# MCU.net
KiCad netlist of a schematic drawn in Altium Designer
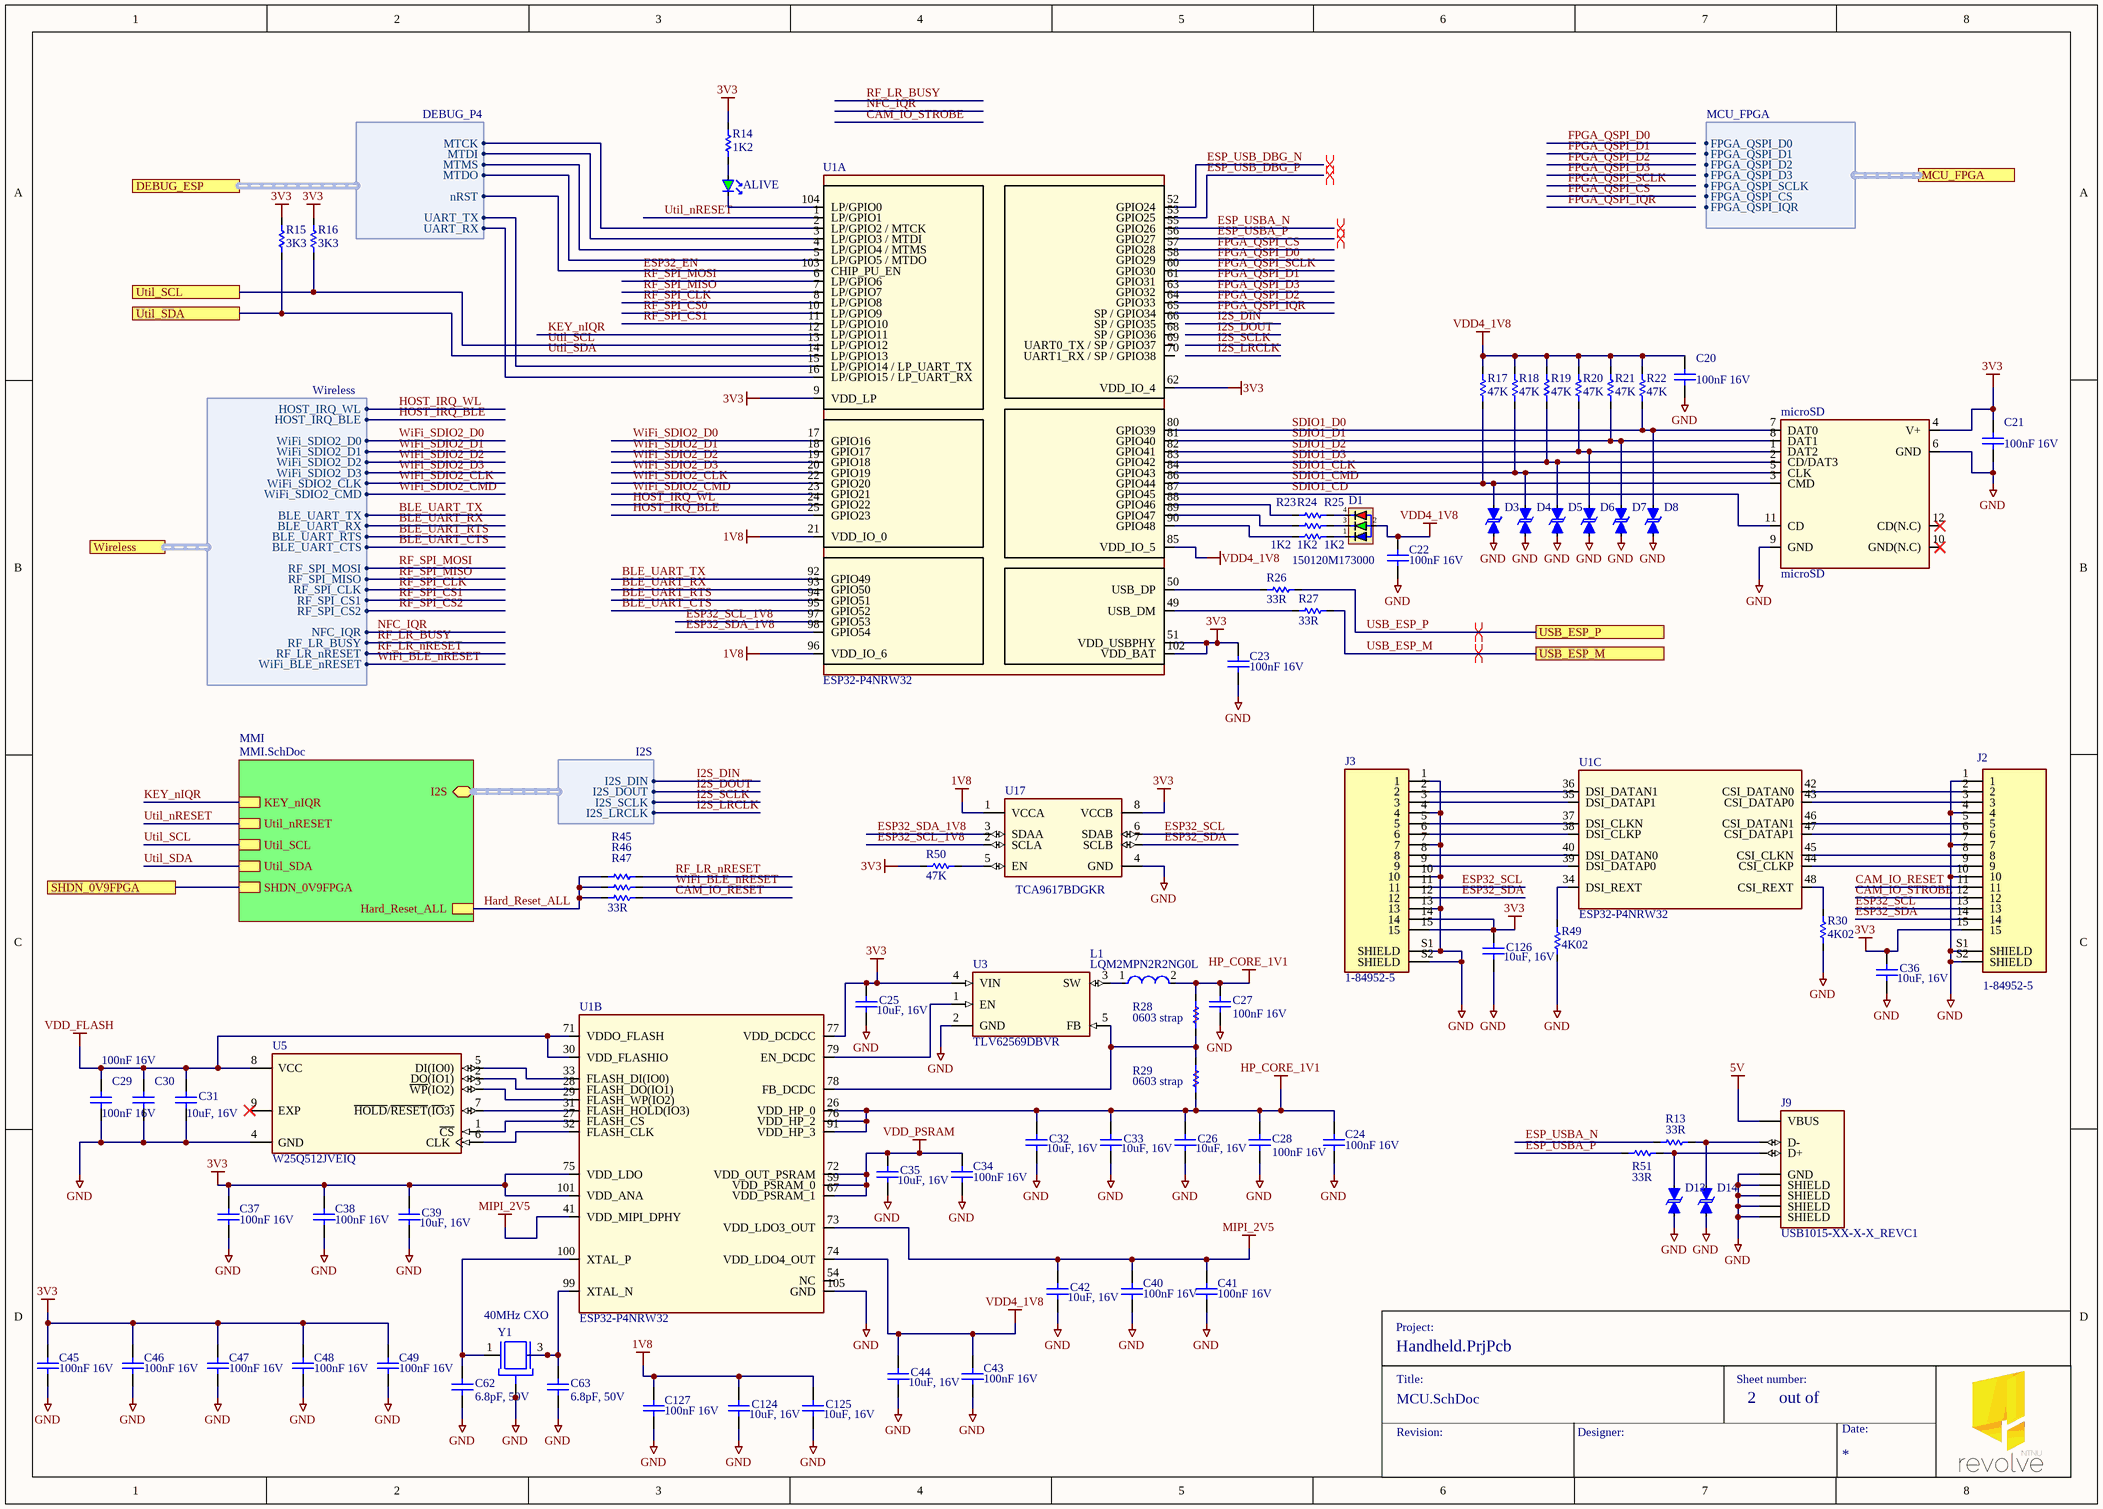
[diagram p0: MCU.SchDoc]

(export (version "E")
  (design (tool "Eeschema 10.0.6"))
  (components
    (comp (ref "ALIVE")
      (value "SMD LED 0603, Green")
      (footprint "LED-0603-RED")
      (description "0603LED-Green")
      (libsource (lib "Eirik Silnes") (part "CMP-001-C10-9"))
    )
    (comp (ref "C20") (value "100nF 16V") (footprint "0402") (libsource (lib "Revolve NTNU") (part "CAP")))
    (comp (ref "C21") (value "100nF 16V") (footprint "0402") (libsource (lib "Revolve NTNU") (part "CAP")))
    (comp (ref "C22") (value "100nF 16V") (footprint "0402") (libsource (lib "Revolve NTNU") (part "CAP")))
    (comp (ref "C23") (value "100nF 16V") (footprint "0402") (libsource (lib "Revolve NTNU") (part "CAP")))
    (comp (ref "C24") (value "100nF 16V") (footprint "0402") (libsource (lib "Revolve NTNU") (part "CAP")))
    (comp (ref "C25")
      (value "10uF, 16V")
      (footprint "0603 Capacitor")
      (description "10uF, 16V, 20%, X5R, 0603")
      (libsource (lib "Revolve NTNU") (part "CAP"))
    )
    (comp (ref "C26")
      (value "10uF, 16V")
      (footprint "0603 Capacitor")
      (description "10uF, 16V, 20%, X5R, 0603")
      (libsource (lib "Revolve NTNU") (part "CAP"))
    )
    (comp (ref "C27") (value "100nF 16V") (footprint "0402") (libsource (lib "Revolve NTNU") (part "CAP")))
    (comp (ref "C28") (value "100nF 16V") (footprint "0402") (libsource (lib "Revolve NTNU") (part "CAP")))
    (comp (ref "C29") (value "100nF 16V") (footprint "0402") (libsource (lib "Revolve NTNU") (part "CAP")))
    (comp (ref "C30") (value "100nF 16V") (footprint "0402") (libsource (lib "Revolve NTNU") (part "CAP")))
    (comp (ref "C31")
      (value "10uF, 16V")
      (footprint "0603 Capacitor")
      (description "10uF, 16V, 20%, X5R, 0603")
      (libsource (lib "Revolve NTNU") (part "CAP"))
    )
    (comp (ref "C32")
      (value "10uF, 16V")
      (footprint "0603 Capacitor")
      (description "10uF, 16V, 20%, X5R, 0603")
      (libsource (lib "Revolve NTNU") (part "CAP"))
    )
    (comp (ref "C33")
      (value "10uF, 16V")
      (footprint "0603 Capacitor")
      (description "10uF, 16V, 20%, X5R, 0603")
      (libsource (lib "Revolve NTNU") (part "CAP"))
    )
    (comp (ref "C34") (value "100nF 16V") (footprint "0402") (libsource (lib "Revolve NTNU") (part "CAP")))
    (comp (ref "C35")
      (value "10uF, 16V")
      (footprint "0603 Capacitor")
      (description "10uF, 16V, 20%, X5R, 0603")
      (libsource (lib "Revolve NTNU") (part "CAP"))
    )
    (comp (ref "C36")
      (value "10uF, 16V")
      (footprint "0603 Capacitor")
      (description "10uF, 16V, 20%, X5R, 0603")
      (libsource (lib "Revolve NTNU") (part "CAP"))
    )
    (comp (ref "C37") (value "100nF 16V") (footprint "0402") (libsource (lib "Revolve NTNU") (part "CAP")))
    (comp (ref "C38") (value "100nF 16V") (footprint "0402") (libsource (lib "Revolve NTNU") (part "CAP")))
    (comp (ref "C39")
      (value "10uF, 16V")
      (footprint "0603 Capacitor")
      (description "10uF, 16V, 20%, X5R, 0603")
      (libsource (lib "Revolve NTNU") (part "CAP"))
    )
    (comp (ref "C40") (value "100nF 16V") (footprint "0402") (libsource (lib "Revolve NTNU") (part "CAP")))
    (comp (ref "C41") (value "100nF 16V") (footprint "0402") (libsource (lib "Revolve NTNU") (part "CAP")))
    (comp (ref "C42")
      (value "10uF, 16V")
      (footprint "0603 Capacitor")
      (description "10uF, 16V, 20%, X5R, 0603")
      (libsource (lib "Revolve NTNU") (part "CAP"))
    )
    (comp (ref "C43") (value "100nF 16V") (footprint "0402") (libsource (lib "Revolve NTNU") (part "CAP")))
    (comp (ref "C44")
      (value "10uF, 16V")
      (footprint "0603 Capacitor")
      (description "10uF, 16V, 20%, X5R, 0603")
      (libsource (lib "Revolve NTNU") (part "CAP"))
    )
    (comp (ref "C45") (value "100nF 16V") (footprint "0402") (libsource (lib "Revolve NTNU") (part "CAP")))
    (comp (ref "C46") (value "100nF 16V") (footprint "0402") (libsource (lib "Revolve NTNU") (part "CAP")))
    (comp (ref "C47") (value "100nF 16V") (footprint "0402") (libsource (lib "Revolve NTNU") (part "CAP")))
    (comp (ref "C48") (value "100nF 16V") (footprint "0402") (libsource (lib "Revolve NTNU") (part "CAP")))
    (comp (ref "C49") (value "100nF 16V") (footprint "0402") (libsource (lib "Revolve NTNU") (part "CAP")))
    (comp (ref "C62")
      (value "6.8pF, 50V")
      (footprint "0402 resistor")
      (description "6.8pF, 50V, 10%, 0402")
      (libsource (lib "Revolve NTNU") (part "CAP"))
    )
    (comp (ref "C63")
      (value "6.8pF, 50V")
      (footprint "0402 resistor")
      (description "6.8pF, 50V, 10%, 0402")
      (libsource (lib "Revolve NTNU") (part "CAP"))
    )
    (comp (ref "C124")
      (value "10uF, 16V")
      (footprint "0603 Capacitor")
      (description "10uF, 16V, 20%, X5R, 0603")
      (libsource (lib "Revolve NTNU") (part "CAP"))
    )
    (comp (ref "C125")
      (value "10uF, 16V")
      (footprint "0603 Capacitor")
      (description "10uF, 16V, 20%, X5R, 0603")
      (libsource (lib "Revolve NTNU") (part "CAP"))
    )
    (comp (ref "C126")
      (value "10uF, 16V")
      (footprint "0603 Capacitor")
      (description "10uF, 16V, 20%, X5R, 0603")
      (libsource (lib "Revolve NTNU") (part "CAP"))
    )
    (comp (ref "C127") (value "100nF 16V") (footprint "0402") (libsource (lib "Revolve NTNU") (part "CAP")))
    (comp (ref "D1")
      (value "150120M173000")
      (footprint "WL-SFCW_1206")
      (description "Led, Red/Green/Blue, 360Mcd/1Cd/350Mcd Rohs Compliant: Yes")
      (libsource (lib "Eirik Silnes") (part "WL-SFCW_type 2"))
    )
    (comp (ref "D3")
      (value "DESD3V3E1BL-7B")
      (footprint "CR_X1-DFN1006-2_DIO-M")
      (description "TVS DIODE 3.3V, DFN1006-2, 13pF @ 1MHz")
      (fields (field (name "COPYRIGHT") "Copyright (C) 2025 Ultra Librarian. All rights reserved."))
      (libsource (lib "Handheld") (part "DESD3V3E1BL-7B"))
    )
    (comp (ref "D4")
      (value "DESD3V3E1BL-7B")
      (footprint "CR_X1-DFN1006-2_DIO-M")
      (description "TVS DIODE 3.3V, DFN1006-2, 13pF @ 1MHz")
      (fields (field (name "COPYRIGHT") "Copyright (C) 2025 Ultra Librarian. All rights reserved."))
      (libsource (lib "Handheld") (part "DESD3V3E1BL-7B"))
    )
    (comp (ref "D5")
      (value "DESD3V3E1BL-7B")
      (footprint "CR_X1-DFN1006-2_DIO-M")
      (description "TVS DIODE 3.3V, DFN1006-2, 13pF @ 1MHz")
      (fields (field (name "COPYRIGHT") "Copyright (C) 2025 Ultra Librarian. All rights reserved."))
      (libsource (lib "Handheld") (part "DESD3V3E1BL-7B"))
    )
    (comp (ref "D6")
      (value "DESD3V3E1BL-7B")
      (footprint "CR_X1-DFN1006-2_DIO-M")
      (description "TVS DIODE 3.3V, DFN1006-2, 13pF @ 1MHz")
      (fields (field (name "COPYRIGHT") "Copyright (C) 2025 Ultra Librarian. All rights reserved."))
      (libsource (lib "Handheld") (part "DESD3V3E1BL-7B"))
    )
    (comp (ref "D7")
      (value "DESD3V3E1BL-7B")
      (footprint "CR_X1-DFN1006-2_DIO-M")
      (description "TVS DIODE 3.3V, DFN1006-2, 13pF @ 1MHz")
      (fields (field (name "COPYRIGHT") "Copyright (C) 2025 Ultra Librarian. All rights reserved."))
      (libsource (lib "Handheld") (part "DESD3V3E1BL-7B"))
    )
    (comp (ref "D8")
      (value "DESD3V3E1BL-7B")
      (footprint "CR_X1-DFN1006-2_DIO-M")
      (description "TVS DIODE 3.3V, DFN1006-2, 13pF @ 1MHz")
      (fields (field (name "COPYRIGHT") "Copyright (C) 2025 Ultra Librarian. All rights reserved."))
      (libsource (lib "Handheld") (part "DESD3V3E1BL-7B"))
    )
    (comp (ref "D13")
      (value "DESD3V3E1BL-7B")
      (footprint "CR_X1-DFN1006-2_DIO-M")
      (description "TVS DIODE 3.3V, DFN1006-2, 13pF @ 1MHz")
      (fields (field (name "COPYRIGHT") "Copyright (C) 2025 Ultra Librarian. All rights reserved."))
      (libsource (lib "Handheld") (part "DESD3V3E1BL-7B"))
    )
    (comp (ref "D14")
      (value "DESD3V3E1BL-7B")
      (footprint "CR_X1-DFN1006-2_DIO-M")
      (description "TVS DIODE 3.3V, DFN1006-2, 13pF @ 1MHz")
      (fields (field (name "COPYRIGHT") "Copyright (C) 2025 Ultra Librarian. All rights reserved."))
      (libsource (lib "Handheld") (part "DESD3V3E1BL-7B"))
    )
    (comp (ref "J2")
      (value "1-84952-5")
      (footprint "TE_1-84952-5")
      (description "Conn FPC Connector SKT 15 POS 1mm Solder RA SMD T/R")
      (fields (field (name "MF") "TE Connectivity"))
      (libsource (lib "Handheld") (part "1-84952-5"))
    )
    (comp (ref "J3")
      (value "1-84952-5")
      (footprint "TE_1-84952-5")
      (description "Conn FPC Connector SKT 15 POS 1mm Solder RA SMD T/R")
      (fields (field (name "MF") "TE Connectivity"))
      (libsource (lib "") (part "1-84952-5_1"))
    )
    (comp (ref "J9")
      (value "USB1015-XX-X-X_REVC1")
      (footprint "GCT_USB1015-XX-X-X_REVC1")
      (fields (field (name "MF") "Global Connector Technology") (field (name "MP") "USB1015-GF-L-A"))
      (libsource (lib "Handheld") (part "USB1015-XX-X-X_REVC1"))
    )
    (comp (ref "L1")
      (value "LQM2MPN2R2NG0L")
      (footprint "FP-LQM2MPN_G0-IPC_B")
      (description "Inductor Power Chip Shielded Multi-Layer 2.2uH 30% 1MHz Ferrite 1.2A 0.138Ohm DCR 0806 T/R")
      (fields (field (name "TOLERANCE") "30%"))
      (libsource (lib "Eirik Silnes") (part "725321dda6339637d4d059423bc1c3c"))
    )
    (comp (ref "microSD")
      (value "microSD")
      (footprint "Handheld:microSD")
      (description "wurth µSD connector")
      (libsource (lib "Handheld") (part "microSD"))
    )
    (comp (ref "R13")
      (value "33R")
      (footprint "0603 Resistor")
      (description "33R, 1%, 1/10W, 0603")
      (fields (field (name "TOLERANCE") "1%") (field (name "MANUFACTURER") "Panasonic"))
      (libsource (lib "Revolve NTNU") (part "Resistor"))
    )
    (comp (ref "R14")
      (value "1K2")
      (footprint "0603 Resistor")
      (description "1K2, 5%, 1/10W, 0603")
      (libsource (lib "Revolve NTNU") (part "Resistor"))
    )
    (comp (ref "R15")
      (value "3K3")
      (footprint "0603 Resistor")
      (description "3K3, 5%, 1/10W, 0603")
      (libsource (lib "Revolve NTNU") (part "Resistor"))
    )
    (comp (ref "R16")
      (value "3K3")
      (footprint "0603 Resistor")
      (description "3K3, 5%, 1/10W, 0603")
      (libsource (lib "Revolve NTNU") (part "Resistor"))
    )
    (comp (ref "R17")
      (value "47K")
      (footprint "0603 Resistor")
      (description "47K, 1%, 1/10W, 0603")
      (libsource (lib "Revolve NTNU") (part "Resistor"))
    )
    (comp (ref "R18")
      (value "47K")
      (footprint "0603 Resistor")
      (description "47K, 1%, 1/10W, 0603")
      (libsource (lib "Revolve NTNU") (part "Resistor"))
    )
    (comp (ref "R19")
      (value "47K")
      (footprint "0603 Resistor")
      (description "47K, 1%, 1/10W, 0603")
      (libsource (lib "Revolve NTNU") (part "Resistor"))
    )
    (comp (ref "R20")
      (value "47K")
      (footprint "0603 Resistor")
      (description "47K, 1%, 1/10W, 0603")
      (libsource (lib "Revolve NTNU") (part "Resistor"))
    )
    (comp (ref "R21")
      (value "47K")
      (footprint "0603 Resistor")
      (description "47K, 1%, 1/10W, 0603")
      (libsource (lib "Revolve NTNU") (part "Resistor"))
    )
    (comp (ref "R22")
      (value "47K")
      (footprint "0603 Resistor")
      (description "47K, 1%, 1/10W, 0603")
      (libsource (lib "Revolve NTNU") (part "Resistor"))
    )
    (comp (ref "R23")
      (value "1K2")
      (footprint "0603 Resistor")
      (description "1K2, 5%, 1/10W, 0603")
      (libsource (lib "Revolve NTNU") (part "Resistor"))
    )
    (comp (ref "R24")
      (value "1K2")
      (footprint "0603 Resistor")
      (description "1K2, 5%, 1/10W, 0603")
      (libsource (lib "Revolve NTNU") (part "Resistor"))
    )
    (comp (ref "R25")
      (value "1K2")
      (footprint "0603 Resistor")
      (description "1K2, 5%, 1/10W, 0603")
      (libsource (lib "Revolve NTNU") (part "Resistor"))
    )
    (comp (ref "R26")
      (value "33R")
      (footprint "0603 Resistor")
      (description "33R, 1%, 1/10W, 0603")
      (fields (field (name "TOLERANCE") "1%") (field (name "MANUFACTURER") "Panasonic"))
      (libsource (lib "Revolve NTNU") (part "Resistor"))
    )
    (comp (ref "R27")
      (value "33R")
      (footprint "0603 Resistor")
      (description "33R, 1%, 1/10W, 0603")
      (fields (field (name "TOLERANCE") "1%") (field (name "MANUFACTURER") "Panasonic"))
      (libsource (lib "Revolve NTNU") (part "Resistor"))
    )
    (comp (ref "R28")
      (value "0603 strap")
      (footprint "0603 pads")
      (description "No resistor, just the pad")
      (libsource (lib "Revolve NTNU") (part "Component_1"))
    )
    (comp (ref "R29")
      (value "0603 strap")
      (footprint "0603 pads")
      (description "No resistor, just the pad")
      (libsource (lib "Revolve NTNU") (part "Component_1"))
    )
    (comp (ref "R30")
      (value "4K02")
      (footprint "0603 Resistor")
      (description "4K02, 1%, 1/10W, 0603")
      (libsource (lib "Revolve NTNU") (part "Resistor"))
    )
    (comp (ref "R45")
      (value "33R")
      (footprint "0603 Resistor")
      (description "33R, 1%, 1/10W, 0603")
      (fields (field (name "TOLERANCE") "1%") (field (name "MANUFACTURER") "Panasonic"))
      (libsource (lib "Revolve NTNU") (part "Resistor"))
    )
    (comp (ref "R46")
      (value "33R")
      (footprint "0603 Resistor")
      (description "33R, 1%, 1/10W, 0603")
      (fields (field (name "TOLERANCE") "1%") (field (name "MANUFACTURER") "Panasonic"))
      (libsource (lib "Revolve NTNU") (part "Resistor"))
    )
    (comp (ref "R47")
      (value "33R")
      (footprint "0603 Resistor")
      (description "33R, 1%, 1/10W, 0603")
      (fields (field (name "TOLERANCE") "1%") (field (name "MANUFACTURER") "Panasonic"))
      (libsource (lib "Revolve NTNU") (part "Resistor"))
    )
    (comp (ref "R49")
      (value "4K02")
      (footprint "0603 Resistor")
      (description "4K02, 1%, 1/10W, 0603")
      (libsource (lib "Revolve NTNU") (part "Resistor"))
    )
    (comp (ref "R50")
      (value "47K")
      (footprint "0603 Resistor")
      (description "47K, 1%, 1/10W, 0603")
      (libsource (lib "Revolve NTNU") (part "Resistor"))
    )
    (comp (ref "R51")
      (value "33R")
      (footprint "0603 Resistor")
      (description "33R, 1%, 1/10W, 0603")
      (fields (field (name "TOLERANCE") "1%") (field (name "MANUFACTURER") "Panasonic"))
      (libsource (lib "Revolve NTNU") (part "Resistor"))
    )
    (comp (ref "U1")
      (value "ESP32-P4NRW32")
      (footprint "QFN35P1000X1000X85_HS-105M")
      (description "RISC-V 32-bit dual-core 360MHz,  32MB PSRAM, 55xGPIO")
      (libsource (lib "Handheld") (part "ESP32-P4NRW32-R09.0.1"))
    )
    (comp (ref "U3")
      (value "TLV62569DBVR")
      (footprint "SOT95P280X145-5N")
      (description "2.5V-5.5V input, 2-A high efficiency step-down buck converter in SOT23 and SOT563 package")
      (fields (field (name "MF") "Texas Instruments"))
      (libsource (lib "Handheld") (part "TLV62569DBVR"))
    )
    (comp (ref "U5")
      (value "W25Q512JVEIQ")
      (footprint "SON127P600X800X80-9N")
      (description "FLASH - NOR Memory IC 512Mb (64M x 8) SPI - Quad I/O 133 MHz 8-WSON (8x6)")
      (fields (field (name "MF") "Winbond Electronics"))
      (libsource (lib "Handheld") (part "W25Q512JVEIQ"))
    )
    (comp (ref "U17")
      (value "TCA9617BDGKR")
      (footprint "SOP65P490X110-8N")
      (description "2-bit level-translating 1-MHz I2C/SMBus buffer/repeater with powered-off high-impedance")
      (fields (field (name "MF") "Texas Instruments"))
      (libsource (lib "Handheld") (part "TCA9617BDGKR"))
    )
    (comp (ref "Y1")
      (value "40MHz CXO")
      (footprint "XTAL_ECS-400-10-37B2-CKM-TR")
      (description "Crystal 40MHz ±10ppm (Tol) ±10ppm (Stability) 10pF FUND 40Ohm 4-Pin Mini-CSMD T/R")
      (fields (field (name "MF") "ECS Inc.") (field (name "MP") "ECS-400-10-37B2-CKM-TR"))
      (libsource (lib "Handheld") (part "ECS-400-10-37B2-CKM-TR"))
    )
  )
  (nets
    (net (code "5") (name "/BLE_UART_CTS") (class "Default")
      (node (ref "U1") (pin "95") (pinfunction "GPIO52_95") (pintype "passive"))
    )
    (net (code "6") (name "/BLE_UART_RTS") (class "Default")
      (node (ref "U1") (pin "94") (pinfunction "GPIO51_94") (pintype "passive"))
    )
    (net (code "7") (name "/BLE_UART_RX") (class "Default")
      (node (ref "U1") (pin "93") (pinfunction "GPIO50_93") (pintype "passive"))
    )
    (net (code "8") (name "/BLE_UART_TX") (class "Default")
      (node (ref "U1") (pin "92") (pinfunction "GPIO49_92") (pintype "passive"))
    )
    (net (code "9") (name "/CAM_IO_RESET") (class "Default")
      (node (ref "J2") (pin "11") (pinfunction "11_11") (pintype "passive"))
      (node (ref "R47") (pin "2") (pinfunction "2_2") (pintype "passive"))
    )
    (net (code "10") (name "/CAM_IO_STROBE") (class "Default")
      (node (ref "J2") (pin "12") (pinfunction "12_12") (pintype "passive"))
    )
    (net (code "11") (name "/ESP32_EN") (class "Default")
      (node (ref "U1") (pin "103") (pinfunction "CHIP_PU_EN_103") (pintype "passive"))
    )
    (net (code "12") (name "/ESP32_SCL") (class "Default")
      (node (ref "J2") (pin "13") (pinfunction "13_13") (pintype "passive"))
      (node (ref "J3") (pin "11") (pinfunction "11_11") (pintype "passive"))
      (node (ref "U17") (pin "6") (pinfunction "SDAB_6") (pintype "bidirectional"))
    )
    (net (code "13") (name "/ESP32_SCL_1V8") (class "Default")
      (node (ref "U1") (pin "97") (pinfunction "GPIO53_97") (pintype "passive"))
      (node (ref "U17") (pin "2") (pinfunction "SCLA_2") (pintype "bidirectional"))
    )
    (net (code "14") (name "/ESP32_SDA") (class "Default")
      (node (ref "J2") (pin "14") (pinfunction "14_14") (pintype "passive"))
      (node (ref "J3") (pin "12") (pinfunction "12_12") (pintype "passive"))
      (node (ref "U17") (pin "7") (pinfunction "SCLB_7") (pintype "bidirectional"))
    )
    (net (code "15") (name "/ESP32_SDA_1V8") (class "Default")
      (node (ref "U1") (pin "98") (pinfunction "GPIO54_98") (pintype "passive"))
      (node (ref "U17") (pin "3") (pinfunction "SDAA_3") (pintype "bidirectional"))
    )
    (net (code "16") (name "/ESP_USBA_N") (class "Default")
      (node (ref "R13") (pin "1") (pinfunction "1_1") (pintype "passive"))
      (node (ref "U1") (pin "55") (pinfunction "GPIO26_55") (pintype "passive"))
    )
    (net (code "17") (name "/ESP_USBA_P") (class "Default")
      (node (ref "R51") (pin "1") (pinfunction "1_1") (pintype "passive"))
      (node (ref "U1") (pin "56") (pinfunction "GPIO27_56") (pintype "passive"))
    )
    (net (code "18") (name "/ESP_USB_DBG_N") (class "Default")
      (node (ref "U1") (pin "52") (pinfunction "GPIO24_52") (pintype "passive"))
    )
    (net (code "19") (name "/ESP_USB_DBG_P") (class "Default")
      (node (ref "U1") (pin "53") (pinfunction "GPIO25_53") (pintype "passive"))
    )
    (net (code "20") (name "/FPGA_QSPI_CS") (class "Default")
      (node (ref "U1") (pin "57") (pinfunction "GPIO28_57") (pintype "passive"))
    )
    (net (code "21") (name "/FPGA_QSPI_D0") (class "Default")
      (node (ref "U1") (pin "58") (pinfunction "GPIO29_58") (pintype "passive"))
    )
    (net (code "22") (name "/FPGA_QSPI_D1") (class "Default")
      (node (ref "U1") (pin "61") (pinfunction "GPIO31_61") (pintype "passive"))
    )
    (net (code "23") (name "/FPGA_QSPI_D2") (class "Default")
      (node (ref "U1") (pin "64") (pinfunction "GPIO33_64") (pintype "passive"))
    )
    (net (code "24") (name "/FPGA_QSPI_D3") (class "Default")
      (node (ref "U1") (pin "63") (pinfunction "GPIO32_63") (pintype "passive"))
    )
    (net (code "25") (name "/FPGA_QSPI_IQR") (class "Default")
      (node (ref "U1") (pin "65") (pinfunction "SP_/_GPIO34_65") (pintype "passive"))
    )
    (net (code "26") (name "/FPGA_QSPI_SCLK") (class "Default")
      (node (ref "U1") (pin "60") (pinfunction "GPIO30_60") (pintype "passive"))
    )
    (net (code "27") (name "/HOST_IRQ_BLE") (class "Default")
      (node (ref "U1") (pin "25") (pinfunction "GPIO23_25") (pintype "passive"))
    )
    (net (code "28") (name "/HOST_IRQ_WL") (class "Default")
      (node (ref "U1") (pin "24") (pinfunction "GPIO22_24") (pintype "passive"))
    )
    (net (code "29") (name "/Hard_Reset_ALL") (class "Default")
      (node (ref "R45") (pin "1") (pinfunction "1_1") (pintype "passive"))
      (node (ref "R46") (pin "1") (pinfunction "1_1") (pintype "passive"))
      (node (ref "R47") (pin "1") (pinfunction "1_1") (pintype "passive"))
    )
    (net (code "34") (name "/KEY_nIQR") (class "Default")
      (node (ref "U1") (pin "12") (pinfunction "LP/GPIO11_12") (pintype "passive"))
    )
    (net (code "35") (name "/MTCK") (class "Default")
      (node (ref "U1") (pin "2") (pinfunction "LP/GPIO2_/_MTCK_2") (pintype "passive"))
    )
    (net (code "36") (name "/MTDI") (class "Default")
      (node (ref "U1") (pin "3") (pinfunction "LP/GPIO3_/_MTDI_3") (pintype "passive"))
    )
    (net (code "37") (name "/MTDO") (class "Default")
      (node (ref "U1") (pin "5") (pinfunction "LP/GPIO5_/_MTDO_5") (pintype "passive"))
    )
    (net (code "38") (name "/MTMS") (class "Default")
      (node (ref "U1") (pin "4") (pinfunction "LP/GPIO4_/_MTMS_4") (pintype "passive"))
    )
    (net (code "41") (name "/RF_LR_nRESET") (class "Default")
      (node (ref "R45") (pin "2") (pinfunction "2_2") (pintype "passive"))
    )
    (net (code "42") (name "/RF_SPI_CLK") (class "Default")
      (node (ref "U1") (pin "8") (pinfunction "LP/GPIO8_8") (pintype "passive"))
    )
    (net (code "43") (name "/RF_SPI_CS0") (class "Default")
      (node (ref "U1") (pin "10") (pinfunction "LP/GPIO9_10") (pintype "passive"))
    )
    (net (code "44") (name "/RF_SPI_CS1") (class "Default")
      (node (ref "U1") (pin "11") (pinfunction "LP/GPIO10_11") (pintype "passive"))
    )
    (net (code "46") (name "/RF_SPI_MISO") (class "Default")
      (node (ref "U1") (pin "7") (pinfunction "LP/GPIO7_7") (pintype "passive"))
    )
    (net (code "47") (name "/RF_SPI_MOSI") (class "Default")
      (node (ref "U1") (pin "6") (pinfunction "LP/GPIO6_6") (pintype "passive"))
    )
    (net (code "48") (name "/SDIO1_CD") (class "Default")
      (node (ref "U1") (pin "87") (pinfunction "GPIO45_87") (pintype "passive"))
      (node (ref "microSD") (pin "11") (pinfunction "CD_11") (pintype "passive"))
    )
    (net (code "49") (name "/SDIO1_CLK") (class "Default")
      (node (ref "D4") (pin "1") (pinfunction "CATHODE_1") (pintype "passive"))
      (node (ref "R18") (pin "2") (pinfunction "2_2") (pintype "passive"))
      (node (ref "U1") (pin "84") (pinfunction "GPIO43_84") (pintype "passive"))
      (node (ref "microSD") (pin "5") (pinfunction "CLK_5") (pintype "passive"))
    )
    (net (code "50") (name "/SDIO1_CMD") (class "Default")
      (node (ref "D3") (pin "1") (pinfunction "CATHODE_1") (pintype "passive"))
      (node (ref "R17") (pin "2") (pinfunction "2_2") (pintype "passive"))
      (node (ref "U1") (pin "86") (pinfunction "GPIO44_86") (pintype "passive"))
      (node (ref "microSD") (pin "3") (pinfunction "CMD_3") (pintype "passive"))
    )
    (net (code "51") (name "/SDIO1_D0") (class "Default")
      (node (ref "D8") (pin "1") (pinfunction "CATHODE_1") (pintype "passive"))
      (node (ref "R22") (pin "2") (pinfunction "2_2") (pintype "passive"))
      (node (ref "U1") (pin "80") (pinfunction "GPIO39_80") (pintype "passive"))
      (node (ref "microSD") (pin "7") (pinfunction "DAT0_7") (pintype "passive"))
    )
    (net (code "52") (name "/SDIO1_D1") (class "Default")
      (node (ref "D7") (pin "1") (pinfunction "CATHODE_1") (pintype "passive"))
      (node (ref "R21") (pin "2") (pinfunction "2_2") (pintype "passive"))
      (node (ref "U1") (pin "81") (pinfunction "GPIO40_81") (pintype "passive"))
      (node (ref "microSD") (pin "8") (pinfunction "DAT1_8") (pintype "passive"))
    )
    (net (code "53") (name "/SDIO1_D2") (class "Default")
      (node (ref "D6") (pin "1") (pinfunction "CATHODE_1") (pintype "passive"))
      (node (ref "R20") (pin "2") (pinfunction "2_2") (pintype "passive"))
      (node (ref "U1") (pin "82") (pinfunction "GPIO41_82") (pintype "passive"))
      (node (ref "microSD") (pin "1") (pinfunction "DAT2_1") (pintype "passive"))
    )
    (net (code "54") (name "/SDIO1_D3") (class "Default")
      (node (ref "D5") (pin "1") (pinfunction "CATHODE_1") (pintype "passive"))
      (node (ref "R19") (pin "2") (pinfunction "2_2") (pintype "passive"))
      (node (ref "U1") (pin "83") (pinfunction "GPIO42_83") (pintype "passive"))
      (node (ref "microSD") (pin "2") (pinfunction "CD/DAT3_2") (pintype "passive"))
    )
    (net (code "56") (name "/UART_RX") (class "Default")
      (node (ref "U1") (pin "16") (pinfunction "LP/GPIO15_/_LP_UART_RX_16") (pintype "passive"))
    )
    (net (code "57") (name "/UART_TX") (class "Default")
      (node (ref "U1") (pin "15") (pinfunction "LP/GPIO14_/_LP_UART_TX_15") (pintype "passive"))
    )
    (net (code "58") (name "/USB_ESP_M") (class "Default")
      (node (ref "R27") (pin "2") (pinfunction "2_2") (pintype "passive"))
    )
    (net (code "59") (name "/USB_ESP_P") (class "Default")
      (node (ref "R26") (pin "2") (pinfunction "2_2") (pintype "passive"))
    )
    (net (code "60") (name "/Util_SCL") (class "Default")
      (node (ref "R16") (pin "1") (pinfunction "1_1") (pintype "passive"))
      (node (ref "U1") (pin "13") (pinfunction "LP/GPIO12_13") (pintype "passive"))
    )
    (net (code "61") (name "/Util_SDA") (class "Default")
      (node (ref "R15") (pin "1") (pinfunction "1_1") (pintype "passive"))
      (node (ref "U1") (pin "14") (pinfunction "LP/GPIO13_14") (pintype "passive"))
    )
    (net (code "62") (name "/Util_nRESET") (class "Default")
      (node (ref "U1") (pin "1") (pinfunction "LP/GPIO1_1") (pintype "passive"))
    )
    (net (code "63") (name "/WiFi_BLE_nRESET") (class "Default")
      (node (ref "R46") (pin "2") (pinfunction "2_2") (pintype "passive"))
    )
    (net (code "64") (name "/WiFi_SDIO2_CLK") (class "Default")
      (node (ref "U1") (pin "22") (pinfunction "GPIO20_22") (pintype "passive"))
    )
    (net (code "65") (name "/WiFi_SDIO2_CMD") (class "Default")
      (node (ref "U1") (pin "23") (pinfunction "GPIO21_23") (pintype "passive"))
    )
    (net (code "66") (name "/WiFi_SDIO2_D0") (class "Default")
      (node (ref "U1") (pin "17") (pinfunction "GPIO16_17") (pintype "passive"))
    )
    (net (code "67") (name "/WiFi_SDIO2_D1") (class "Default")
      (node (ref "U1") (pin "18") (pinfunction "GPIO17_18") (pintype "passive"))
    )
    (net (code "68") (name "/WiFi_SDIO2_D2") (class "Default")
      (node (ref "U1") (pin "19") (pinfunction "GPIO18_19") (pintype "passive"))
    )
    (net (code "69") (name "/WiFi_SDIO2_D3") (class "Default")
      (node (ref "U1") (pin "20") (pinfunction "GPIO19_20") (pintype "passive"))
    )
    (net (code "74") (name "1V8") (class "Default")
      (node (ref "C124") (pin "2") (pinfunction "2_2") (pintype "passive"))
      (node (ref "C125") (pin "2") (pinfunction "2_2") (pintype "passive"))
      (node (ref "C127") (pin "2") (pinfunction "2_2") (pintype "passive"))
      (node (ref "U1") (pin "21") (pinfunction "VDD_IO_0_21") (pintype "passive"))
      (node (ref "U1") (pin "96") (pinfunction "VDD_IO_6_96") (pintype "passive"))
      (node (ref "U17") (pin "1") (pinfunction "VCCA_1") (pintype "power_in"))
    )
    (net (code "75") (name "3V3") (class "Default")
      (node (ref "C126") (pin "2") (pinfunction "2_2") (pintype "passive"))
      (node (ref "C21") (pin "2") (pinfunction "2_2") (pintype "passive"))
      (node (ref "C23") (pin "2") (pinfunction "2_2") (pintype "passive"))
      (node (ref "C25") (pin "2") (pinfunction "2_2") (pintype "passive"))
      (node (ref "C36") (pin "2") (pinfunction "2_2") (pintype "passive"))
      (node (ref "C37") (pin "2") (pinfunction "2_2") (pintype "passive"))
      (node (ref "C38") (pin "2") (pinfunction "2_2") (pintype "passive"))
      (node (ref "C39") (pin "2") (pinfunction "2_2") (pintype "passive"))
      (node (ref "C45") (pin "2") (pinfunction "2_2") (pintype "passive"))
      (node (ref "C46") (pin "2") (pinfunction "2_2") (pintype "passive"))
      (node (ref "C47") (pin "2") (pinfunction "2_2") (pintype "passive"))
      (node (ref "C48") (pin "2") (pinfunction "2_2") (pintype "passive"))
      (node (ref "C49") (pin "2") (pinfunction "2_2") (pintype "passive"))
      (node (ref "J2") (pin "15") (pinfunction "15_15") (pintype "passive"))
      (node (ref "J3") (pin "14") (pinfunction "14_14") (pintype "passive"))
      (node (ref "J3") (pin "15") (pinfunction "15_15") (pintype "passive"))
      (node (ref "R14") (pin "2") (pinfunction "2_2") (pintype "passive"))
      (node (ref "R15") (pin "2") (pinfunction "2_2") (pintype "passive"))
      (node (ref "R16") (pin "2") (pinfunction "2_2") (pintype "passive"))
      (node (ref "R50") (pin "1") (pinfunction "1_1") (pintype "passive"))
      (node (ref "U1") (pin "101") (pinfunction "VDD_ANA_101") (pintype "passive"))
      (node (ref "U1") (pin "102") (pinfunction "VDD_BAT_102") (pintype "passive"))
      (node (ref "U1") (pin "51") (pinfunction "VDD_USBPHY_51") (pintype "passive"))
      (node (ref "U1") (pin "62") (pinfunction "VDD_IO_4_62") (pintype "passive"))
      (node (ref "U1") (pin "75") (pinfunction "VDD_LDO_75") (pintype "passive"))
      (node (ref "U1") (pin "77") (pinfunction "VDD_DCDCC_77") (pintype "passive"))
      (node (ref "U1") (pin "9") (pinfunction "VDD_LP_9") (pintype "passive"))
      (node (ref "U17") (pin "8") (pinfunction "VCCB_8") (pintype "power_in"))
      (node (ref "U3") (pin "4") (pinfunction "VIN_4") (pintype "input"))
      (node (ref "microSD") (pin "4") (pinfunction "V+_4") (pintype "passive"))
    )
    (net (code "76") (name "5V") (class "Default")
      (node (ref "J9") (pin "1") (pinfunction "VBUS_1") (pintype "power_in"))
    )
    (net (code "77") (name "GND") (class "Default")
      (node (ref "C124") (pin "1") (pinfunction "1_1") (pintype "passive"))
      (node (ref "C125") (pin "1") (pinfunction "1_1") (pintype "passive"))
      (node (ref "C126") (pin "1") (pinfunction "1_1") (pintype "passive"))
      (node (ref "C127") (pin "1") (pinfunction "1_1") (pintype "passive"))
      (node (ref "C20") (pin "1") (pinfunction "1_1") (pintype "passive"))
      (node (ref "C21") (pin "1") (pinfunction "1_1") (pintype "passive"))
      (node (ref "C22") (pin "1") (pinfunction "1_1") (pintype "passive"))
      (node (ref "C23") (pin "1") (pinfunction "1_1") (pintype "passive"))
      (node (ref "C24") (pin "1") (pinfunction "1_1") (pintype "passive"))
      (node (ref "C25") (pin "1") (pinfunction "1_1") (pintype "passive"))
      (node (ref "C26") (pin "1") (pinfunction "1_1") (pintype "passive"))
      (node (ref "C27") (pin "2") (pinfunction "2_2") (pintype "passive"))
      (node (ref "C28") (pin "2") (pinfunction "2_2") (pintype "passive"))
      (node (ref "C29") (pin "1") (pinfunction "1_1") (pintype "passive"))
      (node (ref "C30") (pin "1") (pinfunction "1_1") (pintype "passive"))
      (node (ref "C31") (pin "1") (pinfunction "1_1") (pintype "passive"))
      (node (ref "C32") (pin "1") (pinfunction "1_1") (pintype "passive"))
      (node (ref "C33") (pin "1") (pinfunction "1_1") (pintype "passive"))
      (node (ref "C34") (pin "1") (pinfunction "1_1") (pintype "passive"))
      (node (ref "C35") (pin "1") (pinfunction "1_1") (pintype "passive"))
      (node (ref "C36") (pin "1") (pinfunction "1_1") (pintype "passive"))
      (node (ref "C37") (pin "1") (pinfunction "1_1") (pintype "passive"))
      (node (ref "C38") (pin "1") (pinfunction "1_1") (pintype "passive"))
      (node (ref "C39") (pin "1") (pinfunction "1_1") (pintype "passive"))
      (node (ref "C40") (pin "1") (pinfunction "1_1") (pintype "passive"))
      (node (ref "C41") (pin "1") (pinfunction "1_1") (pintype "passive"))
      (node (ref "C42") (pin "1") (pinfunction "1_1") (pintype "passive"))
      (node (ref "C43") (pin "1") (pinfunction "1_1") (pintype "passive"))
      (node (ref "C44") (pin "1") (pinfunction "1_1") (pintype "passive"))
      (node (ref "C45") (pin "1") (pinfunction "1_1") (pintype "passive"))
      (node (ref "C46") (pin "1") (pinfunction "1_1") (pintype "passive"))
      (node (ref "C47") (pin "1") (pinfunction "1_1") (pintype "passive"))
      (node (ref "C48") (pin "1") (pinfunction "1_1") (pintype "passive"))
      (node (ref "C49") (pin "1") (pinfunction "1_1") (pintype "passive"))
      (node (ref "C62") (pin "1") (pinfunction "1_1") (pintype "passive"))
      (node (ref "C63") (pin "1") (pinfunction "1_1") (pintype "passive"))
      (node (ref "D13") (pin "2") (pinfunction "ANODE_2") (pintype "passive"))
      (node (ref "D14") (pin "2") (pinfunction "ANODE_2") (pintype "passive"))
      (node (ref "D3") (pin "2") (pinfunction "ANODE_2") (pintype "passive"))
      (node (ref "D4") (pin "2") (pinfunction "ANODE_2") (pintype "passive"))
      (node (ref "D5") (pin "2") (pinfunction "ANODE_2") (pintype "passive"))
      (node (ref "D6") (pin "2") (pinfunction "ANODE_2") (pintype "passive"))
      (node (ref "D7") (pin "2") (pinfunction "ANODE_2") (pintype "passive"))
      (node (ref "D8") (pin "2") (pinfunction "ANODE_2") (pintype "passive"))
      (node (ref "J2") (pin "1") (pinfunction "1_1") (pintype "passive"))
      (node (ref "J2") (pin "10") (pinfunction "10_10") (pintype "passive"))
      (node (ref "J2") (pin "4") (pinfunction "4_4") (pintype "passive"))
      (node (ref "J2") (pin "7") (pinfunction "7_7") (pintype "passive"))
      (node (ref "J2") (pin "S1") (pinfunction "SHIELD_S1") (pintype "passive"))
      (node (ref "J2") (pin "S2") (pinfunction "SHIELD_S2") (pintype "passive"))
      (node (ref "J3") (pin "1") (pinfunction "1_1") (pintype "passive"))
      (node (ref "J3") (pin "10") (pinfunction "10_10") (pintype "passive"))
      (node (ref "J3") (pin "13") (pinfunction "13_13") (pintype "passive"))
      (node (ref "J3") (pin "4") (pinfunction "4_4") (pintype "passive"))
      (node (ref "J3") (pin "7") (pinfunction "7_7") (pintype "passive"))
      (node (ref "J3") (pin "S1") (pinfunction "SHIELD_S1") (pintype "passive"))
      (node (ref "J3") (pin "S2") (pinfunction "SHIELD_S2") (pintype "passive"))
      (node (ref "J9") (pin "4") (pinfunction "GND_4") (pintype "power_in"))
      (node (ref "J9") (pin "SH1") (pinfunction "SHIELD_SH1") (pintype "power_in"))
      (node (ref "J9") (pin "SH2") (pinfunction "SHIELD_SH2") (pintype "power_in"))
      (node (ref "J9") (pin "SH3") (pinfunction "SHIELD_SH3") (pintype "power_in"))
      (node (ref "J9") (pin "SH4") (pinfunction "SHIELD_SH4") (pintype "power_in"))
      (node (ref "R30") (pin "1") (pinfunction "1_1") (pintype "passive"))
      (node (ref "R49") (pin "1") (pinfunction "1_1") (pintype "passive"))
      (node (ref "U1") (pin "105") (pinfunction "GND_105") (pintype "passive"))
      (node (ref "U17") (pin "4") (pinfunction "GND_4") (pintype "power_in"))
      (node (ref "U3") (pin "2") (pinfunction "GND_2") (pintype "power_in"))
      (node (ref "U5") (pin "4") (pinfunction "GND_4") (pintype "power_in"))
      (node (ref "Y1") (pin "2") (pinfunction "GND_2") (pintype "power_in"))
      (node (ref "Y1") (pin "4") (pinfunction "GND_4") (pintype "power_in"))
      (node (ref "microSD") (pin "6") (pinfunction "GND_6") (pintype "passive"))
      (node (ref "microSD") (pin "9") (pinfunction "GND_9") (pintype "passive"))
    )
    (net (code "78") (name "HP_CORE_1V1") (class "Default")
      (node (ref "C24") (pin "2") (pinfunction "2_2") (pintype "passive"))
      (node (ref "C26") (pin "2") (pinfunction "2_2") (pintype "passive"))
      (node (ref "C27") (pin "1") (pinfunction "1_1") (pintype "passive"))
      (node (ref "C28") (pin "1") (pinfunction "1_1") (pintype "passive"))
      (node (ref "C32") (pin "2") (pinfunction "2_2") (pintype "passive"))
      (node (ref "C33") (pin "2") (pinfunction "2_2") (pintype "passive"))
      (node (ref "L1") (pin "2") (pinfunction "2_2") (pintype "passive"))
      (node (ref "R28") (pin "2") (pinfunction "2_2") (pintype "passive"))
      (node (ref "R29") (pin "1") (pinfunction "1_1") (pintype "passive"))
      (node (ref "U1") (pin "26") (pinfunction "VDD_HP_0_26") (pintype "passive"))
      (node (ref "U1") (pin "76") (pinfunction "VDD_HP_2_76") (pintype "passive"))
      (node (ref "U1") (pin "91") (pinfunction "VDD_HP_3_91") (pintype "passive"))
    )
    (net (code "79") (name "MIPI_2V5") (class "Default")
      (node (ref "C40") (pin "2") (pinfunction "2_2") (pintype "passive"))
      (node (ref "C41") (pin "2") (pinfunction "2_2") (pintype "passive"))
      (node (ref "C42") (pin "2") (pinfunction "2_2") (pintype "passive"))
      (node (ref "U1") (pin "41") (pinfunction "VDD_MIPI_DPHY_41") (pintype "passive"))
      (node (ref "U1") (pin "73") (pinfunction "VDD_LDO3_OUT_73") (pintype "passive"))
    )
    (net (code "80") (name "Net-(ALIVE-A)") (class "Default")
      (node (ref "ALIVE") (pin "1") (pinfunction "A_1") (pintype "passive"))
      (node (ref "R14") (pin "1") (pinfunction "1_1") (pintype "passive"))
    )
    (net (code "81") (name "Net-(ALIVE-K)") (class "Default")
      (node (ref "ALIVE") (pin "2") (pinfunction "K_2") (pintype "passive"))
      (node (ref "U1") (pin "104") (pinfunction "LP/GPIO0_104") (pintype "passive"))
    )
    (net (code "82") (name "Net-(D1-3)") (class "Default")
      (node (ref "D1") (pin "4") (pinfunction "3_4") (pintype "passive"))
      (node (ref "R23") (pin "2") (pinfunction "2_2") (pintype "passive"))
    )
    (net (code "83") (name "Net-(D1-4)") (class "Default")
      (node (ref "D1") (pin "3") (pinfunction "4_3") (pintype "passive"))
      (node (ref "R24") (pin "2") (pinfunction "2_2") (pintype "passive"))
    )
    (net (code "84") (name "Net-(D1-5)") (class "Default")
      (node (ref "D1") (pin "1") (pinfunction "5_1") (pintype "passive"))
      (node (ref "R25") (pin "2") (pinfunction "2_2") (pintype "passive"))
    )
    (net (code "85") (name "Net-(D13-CATHODE)") (class "Default")
      (node (ref "D13") (pin "1") (pinfunction "CATHODE_1") (pintype "passive"))
      (node (ref "J9") (pin "3") (pinfunction "D+_3") (pintype "bidirectional"))
      (node (ref "R51") (pin "2") (pinfunction "2_2") (pintype "passive"))
    )
    (net (code "86") (name "Net-(D14-CATHODE)") (class "Default")
      (node (ref "D14") (pin "1") (pinfunction "CATHODE_1") (pintype "passive"))
      (node (ref "J9") (pin "2") (pinfunction "D-_2") (pintype "bidirectional"))
      (node (ref "R13") (pin "2") (pinfunction "2_2") (pintype "passive"))
    )
    (net (code "87") (name "Net-(U1A-GPIO46)") (class "Default")
      (node (ref "R23") (pin "1") (pinfunction "1_1") (pintype "passive"))
      (node (ref "U1") (pin "88") (pinfunction "GPIO46_88") (pintype "passive"))
    )
    (net (code "88") (name "Net-(U1A-GPIO47)") (class "Default")
      (node (ref "R24") (pin "1") (pinfunction "1_1") (pintype "passive"))
      (node (ref "U1") (pin "89") (pinfunction "GPIO47_89") (pintype "passive"))
    )
    (net (code "89") (name "Net-(U1A-GPIO48)") (class "Default")
      (node (ref "R25") (pin "1") (pinfunction "1_1") (pintype "passive"))
      (node (ref "U1") (pin "90") (pinfunction "GPIO48_90") (pintype "passive"))
    )
    (net (code "90") (name "Net-(U1A-USB_DM)") (class "Default")
      (node (ref "R27") (pin "1") (pinfunction "1_1") (pintype "passive"))
      (node (ref "U1") (pin "49") (pinfunction "USB_DM_49") (pintype "passive"))
    )
    (net (code "91") (name "Net-(U1A-USB_DP)") (class "Default")
      (node (ref "R26") (pin "1") (pinfunction "1_1") (pintype "passive"))
      (node (ref "U1") (pin "50") (pinfunction "USB_DP_50") (pintype "passive"))
    )
    (net (code "92") (name "Net-(U1B-EN_DCDC)") (class "Default")
      (node (ref "U1") (pin "79") (pinfunction "EN_DCDC_79") (pintype "passive"))
      (node (ref "U3") (pin "1") (pinfunction "EN_1") (pintype "input"))
    )
    (net (code "93") (name "Net-(U1B-FB_DCDC)") (class "Default")
      (node (ref "R28") (pin "1") (pinfunction "1_1") (pintype "passive"))
      (node (ref "R29") (pin "2") (pinfunction "2_2") (pintype "passive"))
      (node (ref "U1") (pin "78") (pinfunction "FB_DCDC_78") (pintype "passive"))
      (node (ref "U3") (pin "5") (pinfunction "FB_5") (pintype "input"))
    )
    (net (code "94") (name "Net-(U1B-FLASH_CLK)") (class "Default")
      (node (ref "U1") (pin "32") (pinfunction "FLASH_CLK_32") (pintype "passive"))
      (node (ref "U5") (pin "6") (pinfunction "CLK_6") (pintype "input"))
    )
    (net (code "95") (name "Net-(U1B-FLASH_CS)") (class "Default")
      (node (ref "U1") (pin "27") (pinfunction "FLASH_CS_27") (pintype "passive"))
      (node (ref "U5") (pin "1") (pinfunction "~{CS}_1") (pintype "input"))
    )
    (net (code "96") (name "Net-(U1B-FLASH_DI(IO0))") (class "Default")
      (node (ref "U1") (pin "33") (pinfunction "FLASH_DI(IO0)_33") (pintype "passive"))
      (node (ref "U5") (pin "5") (pinfunction "DI(IO0)_5") (pintype "bidirectional"))
    )
    (net (code "97") (name "Net-(U1B-FLASH_DO(IO1))") (class "Default")
      (node (ref "U1") (pin "28") (pinfunction "FLASH_DO(IO1)_28") (pintype "passive"))
      (node (ref "U5") (pin "2") (pinfunction "DO(IO1)_2") (pintype "bidirectional"))
    )
    (net (code "98") (name "Net-(U1B-FLASH_HOLD(IO3))") (class "Default")
      (node (ref "U1") (pin "31") (pinfunction "FLASH_HOLD(IO3)_31") (pintype "passive"))
      (node (ref "U5") (pin "7") (pinfunction "~{HOLD}/~{RESET}(~{IO}3~{)}_7") (pintype "bidirectional"))
    )
    (net (code "99") (name "Net-(U1B-FLASH_WP(IO2))") (class "Default")
      (node (ref "U1") (pin "29") (pinfunction "FLASH_WP(IO2)_29") (pintype "passive"))
      (node (ref "U5") (pin "3") (pinfunction "~{WP}(IO2)_3") (pintype "bidirectional"))
    )
    (net (code "100") (name "Net-(U1B-XTAL_N)") (class "Default")
      (node (ref "C63") (pin "2") (pinfunction "2_2") (pintype "passive"))
      (node (ref "U1") (pin "99") (pinfunction "XTAL_N_99") (pintype "passive"))
      (node (ref "Y1") (pin "3") (pinfunction "OUT/IN_3") (pintype "passive"))
    )
    (net (code "101") (name "Net-(U1B-XTAL_P)") (class "Default")
      (node (ref "C62") (pin "2") (pinfunction "2_2") (pintype "passive"))
      (node (ref "U1") (pin "100") (pinfunction "XTAL_P_100") (pintype "passive"))
      (node (ref "Y1") (pin "1") (pinfunction "IN/OUT_1") (pintype "passive"))
    )
    (net (code "102") (name "Net-(U1C-CSI_CLKN)") (class "Default")
      (node (ref "J2") (pin "8") (pinfunction "8_8") (pintype "passive"))
      (node (ref "U1") (pin "45") (pinfunction "CSI_CLKN_45") (pintype "passive"))
    )
    (net (code "103") (name "Net-(U1C-CSI_CLKP)") (class "Default")
      (node (ref "J2") (pin "9") (pinfunction "9_9") (pintype "passive"))
      (node (ref "U1") (pin "44") (pinfunction "CSI_CLKP_44") (pintype "passive"))
    )
    (net (code "104") (name "Net-(U1C-CSI_DATAN0)") (class "Default")
      (node (ref "J2") (pin "2") (pinfunction "2_2") (pintype "passive"))
      (node (ref "U1") (pin "42") (pinfunction "CSI_DATAN0_42") (pintype "passive"))
    )
    (net (code "105") (name "Net-(U1C-CSI_DATAN1)") (class "Default")
      (node (ref "J2") (pin "5") (pinfunction "5_5") (pintype "passive"))
      (node (ref "U1") (pin "46") (pinfunction "CSI_DATAN1_46") (pintype "passive"))
    )
    (net (code "106") (name "Net-(U1C-CSI_DATAP0)") (class "Default")
      (node (ref "J2") (pin "3") (pinfunction "3_3") (pintype "passive"))
      (node (ref "U1") (pin "43") (pinfunction "CSI_DATAP0_43") (pintype "passive"))
    )
    (net (code "107") (name "Net-(U1C-CSI_DATAP1)") (class "Default")
      (node (ref "J2") (pin "6") (pinfunction "6_6") (pintype "passive"))
      (node (ref "U1") (pin "47") (pinfunction "CSI_DATAP1_47") (pintype "passive"))
    )
    (net (code "108") (name "Net-(U1C-CSI_REXT)") (class "Default")
      (node (ref "R30") (pin "2") (pinfunction "2_2") (pintype "passive"))
      (node (ref "U1") (pin "48") (pinfunction "CSI_REXT_48") (pintype "passive"))
    )
    (net (code "109") (name "Net-(U1C-DSI_CLKN)") (class "Default")
      (node (ref "J3") (pin "5") (pinfunction "5_5") (pintype "passive"))
      (node (ref "U1") (pin "37") (pinfunction "DSI_CLKN_37") (pintype "passive"))
    )
    (net (code "110") (name "Net-(U1C-DSI_CLKP)") (class "Default")
      (node (ref "J3") (pin "6") (pinfunction "6_6") (pintype "passive"))
      (node (ref "U1") (pin "38") (pinfunction "DSI_CLKP_38") (pintype "passive"))
    )
    (net (code "111") (name "Net-(U1C-DSI_DATAN0)") (class "Default")
      (node (ref "J3") (pin "8") (pinfunction "8_8") (pintype "passive"))
      (node (ref "U1") (pin "40") (pinfunction "DSI_DATAN0_40") (pintype "passive"))
    )
    (net (code "112") (name "Net-(U1C-DSI_DATAN1)") (class "Default")
      (node (ref "J3") (pin "2") (pinfunction "2_2") (pintype "passive"))
      (node (ref "U1") (pin "36") (pinfunction "DSI_DATAN1_36") (pintype "passive"))
    )
    (net (code "113") (name "Net-(U1C-DSI_DATAP0)") (class "Default")
      (node (ref "J3") (pin "9") (pinfunction "9_9") (pintype "passive"))
      (node (ref "U1") (pin "39") (pinfunction "DSI_DATAP0_39") (pintype "passive"))
    )
    (net (code "114") (name "Net-(U1C-DSI_DATAP1)") (class "Default")
      (node (ref "J3") (pin "3") (pinfunction "3_3") (pintype "passive"))
      (node (ref "U1") (pin "35") (pinfunction "DSI_DATAP1_35") (pintype "passive"))
    )
    (net (code "115") (name "Net-(U1C-DSI_REXT)") (class "Default")
      (node (ref "R49") (pin "2") (pinfunction "2_2") (pintype "passive"))
      (node (ref "U1") (pin "34") (pinfunction "DSI_REXT_34") (pintype "passive"))
    )
    (net (code "116") (name "Net-(U3-SW)") (class "Default")
      (node (ref "L1") (pin "1") (pinfunction "1_1") (pintype "passive"))
      (node (ref "U3") (pin "3") (pinfunction "SW_3") (pintype "bidirectional"))
    )
    (net (code "117") (name "Net-(U17-EN)") (class "Default")
      (node (ref "R50") (pin "2") (pinfunction "2_2") (pintype "passive"))
      (node (ref "U17") (pin "5") (pinfunction "EN_5") (pintype "bidirectional"))
    )
    (net (code "118") (name "VDD4_1V8") (class "Default")
      (node (ref "C20") (pin "2") (pinfunction "2_2") (pintype "passive"))
      (node (ref "C22") (pin "2") (pinfunction "2_2") (pintype "passive"))
      (node (ref "C43") (pin "2") (pinfunction "2_2") (pintype "passive"))
      (node (ref "C44") (pin "2") (pinfunction "2_2") (pintype "passive"))
      (node (ref "D1") (pin "2") (pinfunction "Anode_2") (pintype "passive"))
      (node (ref "R17") (pin "1") (pinfunction "1_1") (pintype "passive"))
      (node (ref "R18") (pin "1") (pinfunction "1_1") (pintype "passive"))
      (node (ref "R19") (pin "1") (pinfunction "1_1") (pintype "passive"))
      (node (ref "R20") (pin "1") (pinfunction "1_1") (pintype "passive"))
      (node (ref "R21") (pin "1") (pinfunction "1_1") (pintype "passive"))
      (node (ref "R22") (pin "1") (pinfunction "1_1") (pintype "passive"))
      (node (ref "U1") (pin "74") (pinfunction "VDD_LDO4_OUT_74") (pintype "passive"))
      (node (ref "U1") (pin "85") (pinfunction "VDD_IO_5_85") (pintype "passive"))
    )
    (net (code "119") (name "VDD_FLASH") (class "Default")
      (node (ref "C29") (pin "2") (pinfunction "2_2") (pintype "passive"))
      (node (ref "C30") (pin "2") (pinfunction "2_2") (pintype "passive"))
      (node (ref "C31") (pin "2") (pinfunction "2_2") (pintype "passive"))
      (node (ref "U1") (pin "30") (pinfunction "VDD_FLASHIO_30") (pintype "passive"))
      (node (ref "U1") (pin "71") (pinfunction "VDDO_FLASH_71") (pintype "passive"))
      (node (ref "U5") (pin "8") (pinfunction "VCC_8") (pintype "power_in"))
    )
    (net (code "120") (name "VDD_PSRAM") (class "Default")
      (node (ref "C34") (pin "2") (pinfunction "2_2") (pintype "passive"))
      (node (ref "C35") (pin "2") (pinfunction "2_2") (pintype "passive"))
      (node (ref "U1") (pin "59") (pinfunction "VDD_PSRAM_0_59") (pintype "passive"))
      (node (ref "U1") (pin "67") (pinfunction "VDD_PSRAM_1_67") (pintype "passive"))
      (node (ref "U1") (pin "72") (pinfunction "VDD_OUT_PSRAM_72") (pintype "passive"))
    )
    (net (code "121") (name "unconnected-(U1A-SP_{slash}_GPIO35-Pad66)") (class "Default")
      (node (ref "U1") (pin "66") (pinfunction "SP_/_GPIO35_66") (pintype "passive"))
    )
    (net (code "122") (name "unconnected-(U1A-SP_{slash}_GPIO36-Pad68)") (class "Default")
      (node (ref "U1") (pin "68") (pinfunction "SP_/_GPIO36_68") (pintype "passive"))
    )
    (net (code "123") (name "unconnected-(U1A-UART0_TX_{slash}_SP_{slash}_GPIO37-Pad69)") (class "Default")
      (node (ref "U1") (pin "69") (pinfunction "UART0_TX_/_SP_/_GPIO37_69") (pintype "passive"))
    )
    (net (code "124") (name "unconnected-(U1A-UART1_RX_{slash}_SP_{slash}_GPIO38-Pad70)") (class "Default")
      (node (ref "U1") (pin "70") (pinfunction "UART1_RX_/_SP_/_GPIO38_70") (pintype "passive"))
    )
    (net (code "125") (name "unconnected-(U1B-NC-Pad54)") (class "Default")
      (node (ref "U1") (pin "54") (pinfunction "NC_54") (pintype "passive"))
    )
    (net (code "126") (name "unconnected-(U5-EXP-Pad9)") (class "Default")
      (node (ref "U5") (pin "9") (pinfunction "EXP_9") (pintype "passive+no_connect"))
    )
    (net (code "127") (name "unconnected-(microSD-CD(N.C)-Pad12)") (class "Default")
      (node (ref "microSD") (pin "12") (pinfunction "CD(N.C)_12") (pintype "passive+no_connect"))
    )
    (net (code "128") (name "unconnected-(microSD-GND(N.C)-Pad10)") (class "Default")
      (node (ref "microSD") (pin "10") (pinfunction "GND(N.C)_10") (pintype "passive+no_connect"))
    )
  )
)
